# ESP32_with_USBC.net
KiCad netlist of a schematic drawn in Altium Designer
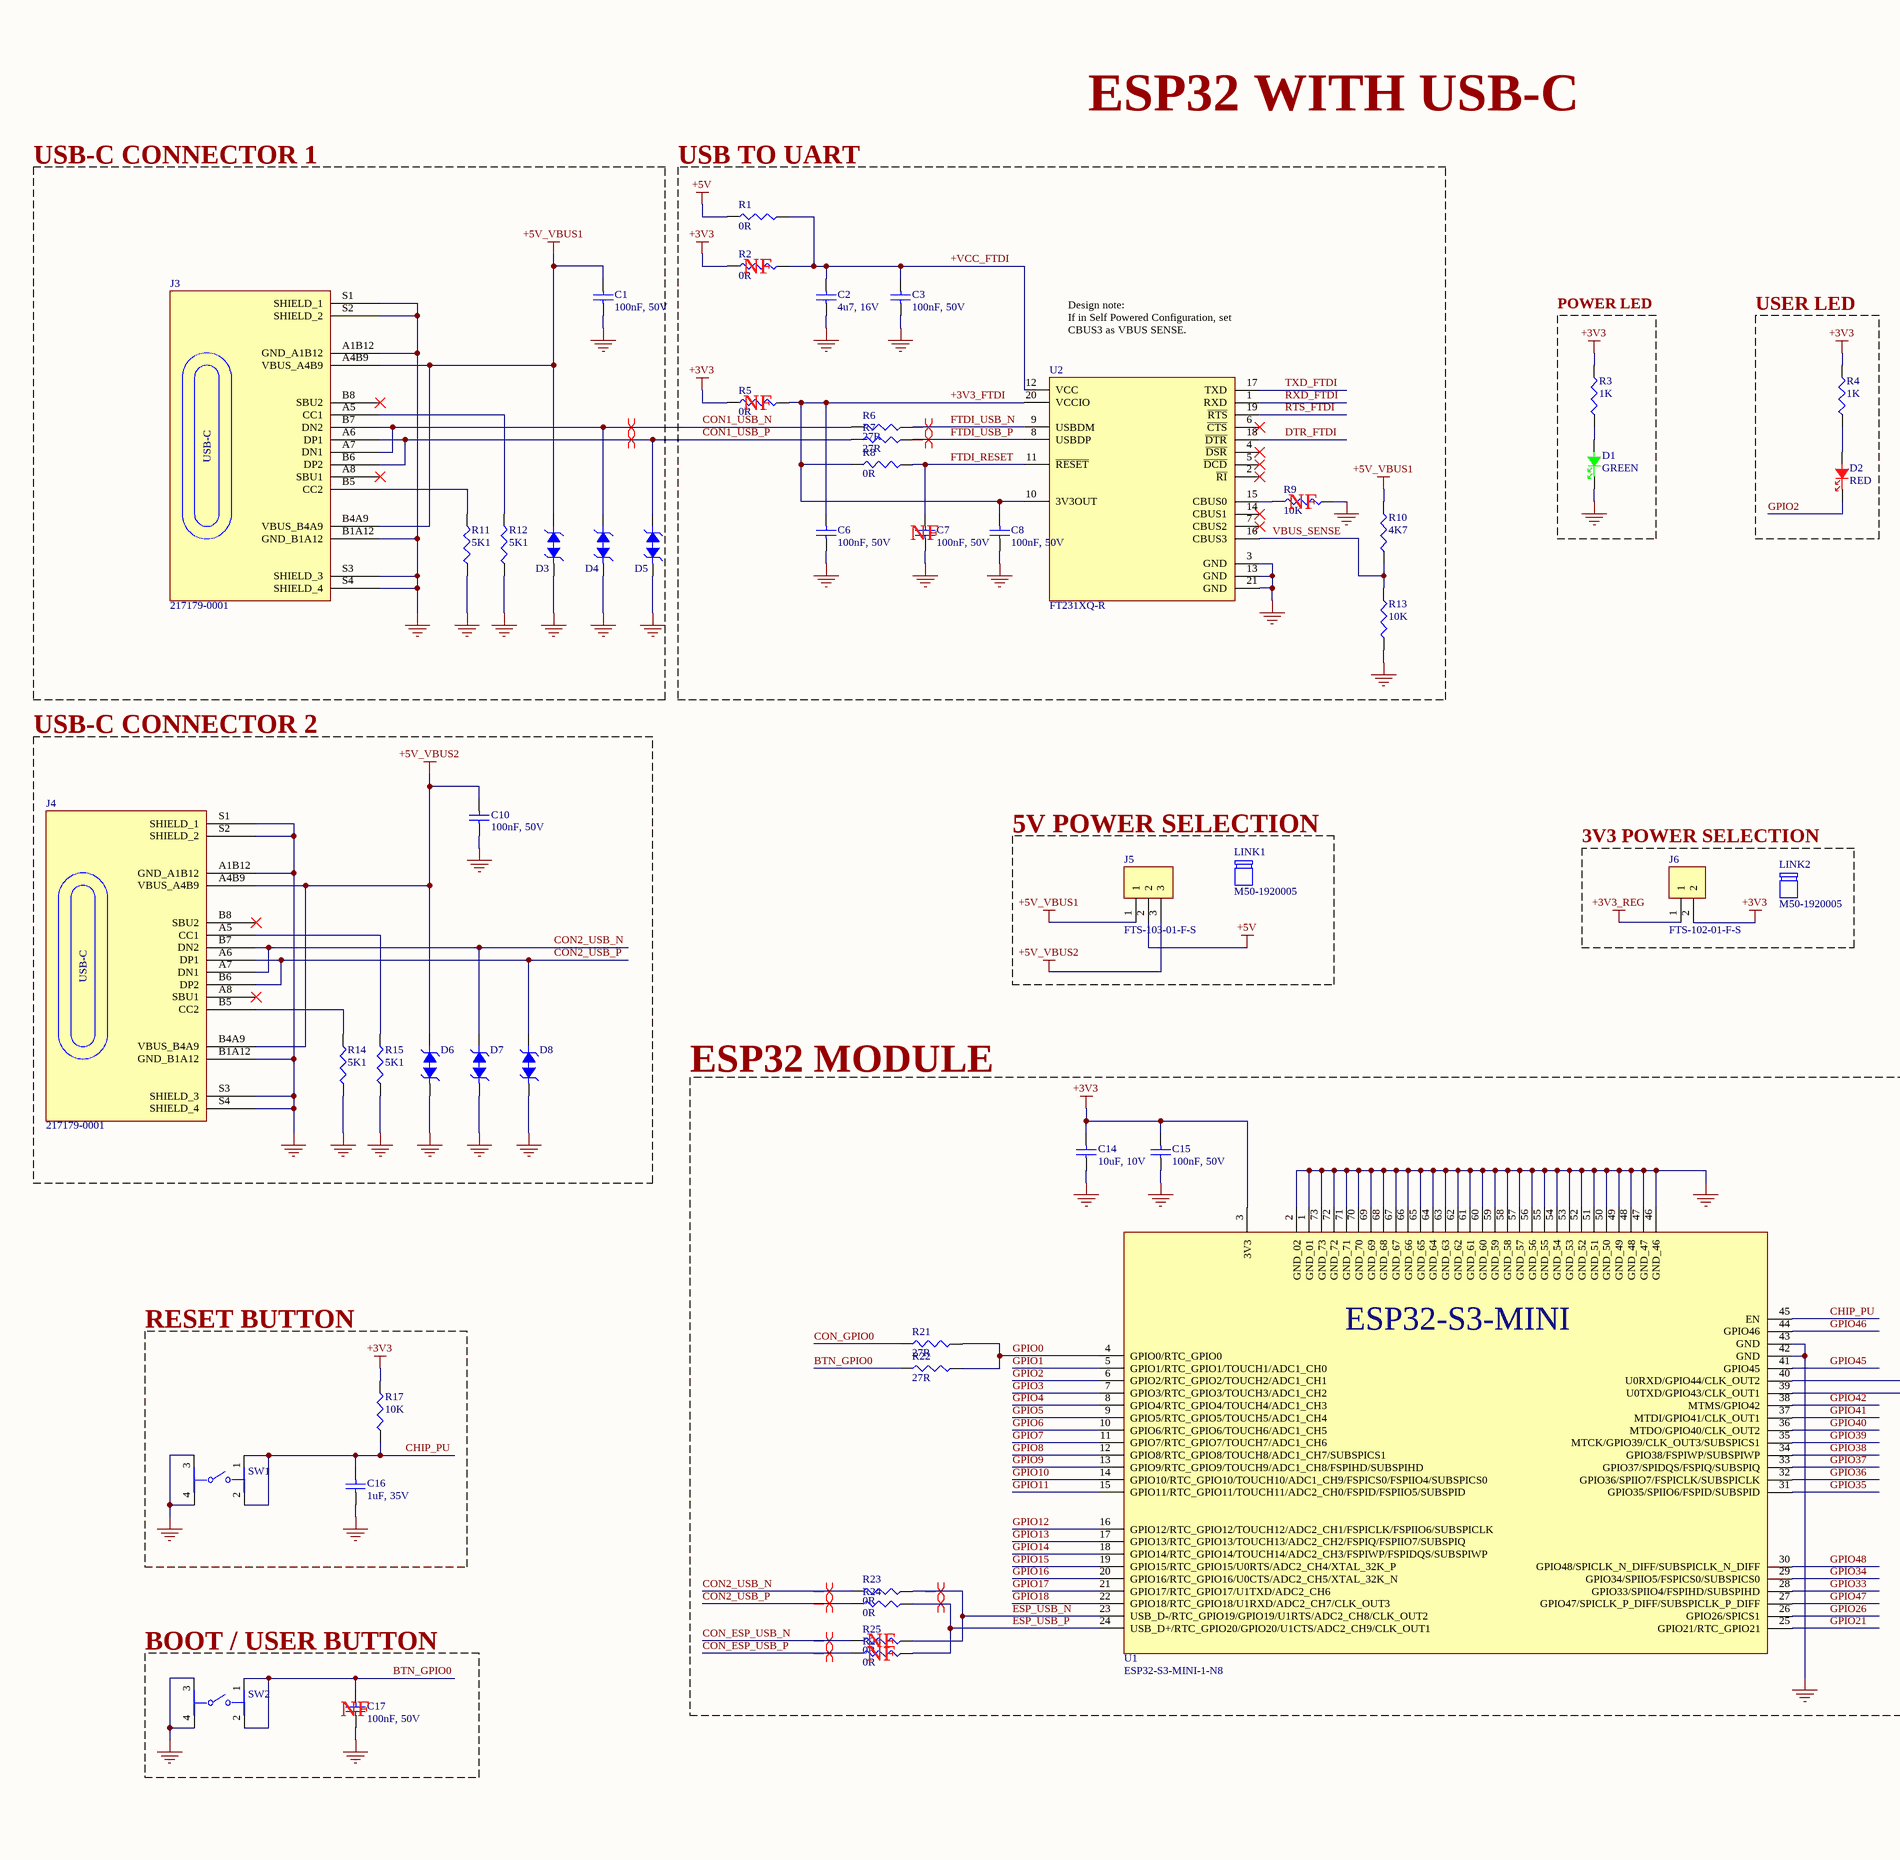
[diagram p0: ESP32 with USBC.SchDoc, left]
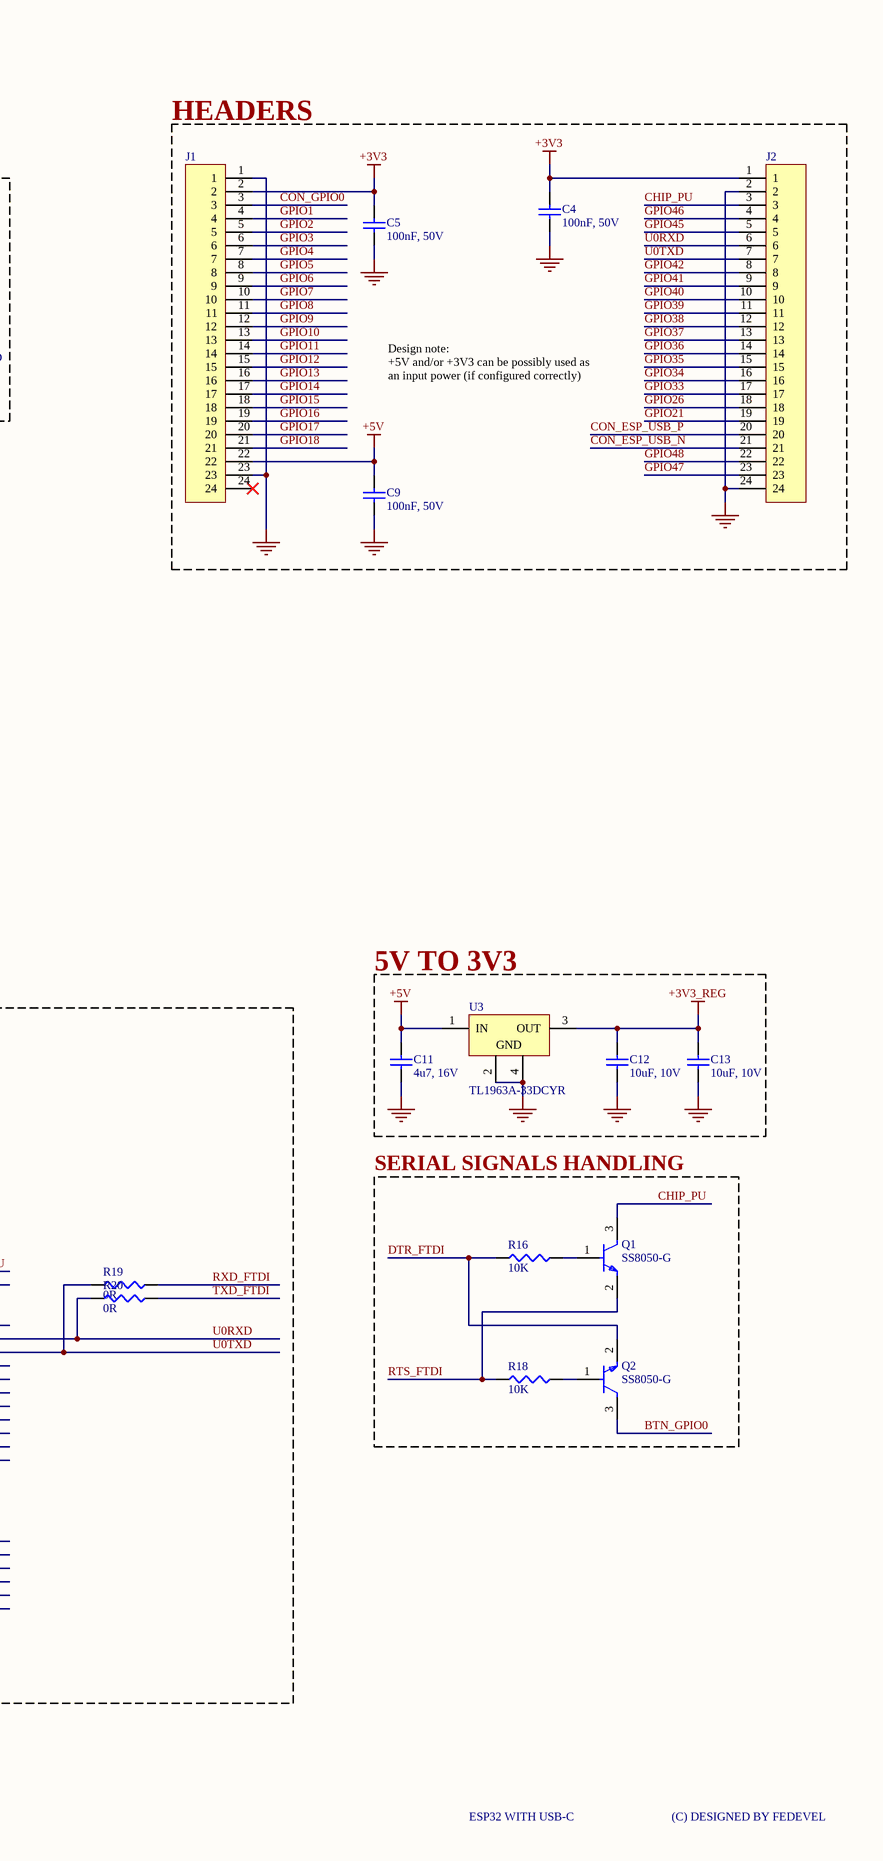
[diagram p1: ESP32 with USBC.SchDoc, right]

(export (version "E")
  (design (tool "Eeschema 10.0.6"))
  (components
    (comp (ref "C1")
      (value "100nF, 50V")
      (footprint "CAPC1005X55N")
      (description "CAP CER 0.1UF 50V X7R 0402")
      (fields
        (field (name "MANUFACTURER") "Samsung")
        (field (name "MANUFACTURER PART NUMBER") "CL05B104KB54PNC")
      )
      (libsource (lib "Schlib") (part "CL05B104KB54PNC"))
    )
    (comp (ref "C2")
      (value "4u7, 16V")
      (footprint "CAPC1005X55N")
      (description "CAP CER 4.7UF 16V X5R 0402")
      (fields
        (field (name "MANUFACTURER") "Samsung")
        (field (name "MANUFACTURER PART NUMBER") "CL05A475MO5NUNC")
      )
      (libsource (lib "Schlib") (part "CL05A475MO5NUNC"))
    )
    (comp (ref "C3")
      (value "100nF, 50V")
      (footprint "CAPC1005X55N")
      (description "CAP CER 0.1UF 50V X7R 0402")
      (fields
        (field (name "MANUFACTURER") "Samsung")
        (field (name "MANUFACTURER PART NUMBER") "CL05B104KB54PNC")
      )
      (libsource (lib "Schlib") (part "CL05B104KB54PNC"))
    )
    (comp (ref "C4")
      (value "100nF, 50V")
      (footprint "CAPC1005X55N")
      (description "CAP CER 0.1UF 50V X7R 0402")
      (fields
        (field (name "MANUFACTURER") "Samsung")
        (field (name "MANUFACTURER PART NUMBER") "CL05B104KB54PNC")
      )
      (libsource (lib "Schlib") (part "CL05B104KB54PNC"))
    )
    (comp (ref "C5")
      (value "100nF, 50V")
      (footprint "CAPC1005X55N")
      (description "CAP CER 0.1UF 50V X7R 0402")
      (fields
        (field (name "MANUFACTURER") "Samsung")
        (field (name "MANUFACTURER PART NUMBER") "CL05B104KB54PNC")
      )
      (libsource (lib "Schlib") (part "CL05B104KB54PNC"))
    )
    (comp (ref "C6")
      (value "100nF, 50V")
      (footprint "CAPC1005X55N")
      (description "CAP CER 0.1UF 50V X7R 0402")
      (fields
        (field (name "MANUFACTURER") "Samsung")
        (field (name "MANUFACTURER PART NUMBER") "CL05B104KB54PNC")
      )
      (libsource (lib "Schlib") (part "CL05B104KB54PNC"))
    )
    (comp (ref "C7")
      (value "100nF, 50V")
      (footprint "CAPC1005X55N")
      (description "CAP CER 0.1UF 50V X7R 0402")
      (fields
        (field (name "MANUFACTURER") "Samsung")
        (field (name "MANUFACTURER PART NUMBER") "CL05B104KB54PNC")
      )
      (libsource (lib "Schlib") (part "CL05B104KB54PNC"))
    )
    (comp (ref "C8")
      (value "100nF, 50V")
      (footprint "CAPC1005X55N")
      (description "CAP CER 0.1UF 50V X7R 0402")
      (fields
        (field (name "MANUFACTURER") "Samsung")
        (field (name "MANUFACTURER PART NUMBER") "CL05B104KB54PNC")
      )
      (libsource (lib "Schlib") (part "CL05B104KB54PNC"))
    )
    (comp (ref "C9")
      (value "100nF, 50V")
      (footprint "CAPC1005X55N")
      (description "CAP CER 0.1UF 50V X7R 0402")
      (fields
        (field (name "MANUFACTURER") "Samsung")
        (field (name "MANUFACTURER PART NUMBER") "CL05B104KB54PNC")
      )
      (libsource (lib "Schlib") (part "CL05B104KB54PNC"))
    )
    (comp (ref "C10")
      (value "100nF, 50V")
      (footprint "CAPC1005X55N")
      (description "CAP CER 0.1UF 50V X7R 0402")
      (fields
        (field (name "MANUFACTURER") "Samsung")
        (field (name "MANUFACTURER PART NUMBER") "CL05B104KB54PNC")
      )
      (libsource (lib "Schlib") (part "CL05B104KB54PNC"))
    )
    (comp (ref "C11")
      (value "4u7, 16V")
      (footprint "CAPC1005X55N")
      (description "CAP CER 4.7UF 16V X5R 0402")
      (fields
        (field (name "MANUFACTURER") "Samsung")
        (field (name "MANUFACTURER PART NUMBER") "CL05A475MO5NUNC")
      )
      (libsource (lib "Schlib") (part "CL05A475MO5NUNC"))
    )
    (comp (ref "C12")
      (value "10uF, 10V")
      (footprint "CAPC1005X55N")
      (description "CAP CER 10UF 10V X5R 0402")
      (fields
        (field (name "MANUFACTURER") "Samsung")
        (field (name "MANUFACTURER PART NUMBER") "CL05A106MP8NUB8")
      )
      (libsource (lib "Schlib") (part "CL05A106MP8NUB8"))
    )
    (comp (ref "C13")
      (value "10uF, 10V")
      (footprint "CAPC1005X55N")
      (description "CAP CER 10UF 10V X5R 0402")
      (fields
        (field (name "MANUFACTURER") "Samsung")
        (field (name "MANUFACTURER PART NUMBER") "CL05A106MP8NUB8")
      )
      (libsource (lib "Schlib") (part "CL05A106MP8NUB8"))
    )
    (comp (ref "C14")
      (value "10uF, 10V")
      (footprint "CAPC1005X55N")
      (description "CAP CER 10UF 10V X5R 0402")
      (fields
        (field (name "MANUFACTURER") "Samsung")
        (field (name "MANUFACTURER PART NUMBER") "CL05A106MP8NUB8")
      )
      (libsource (lib "Schlib") (part "CL05A106MP8NUB8"))
    )
    (comp (ref "C15")
      (value "100nF, 50V")
      (footprint "CAPC1005X55N")
      (description "CAP CER 0.1UF 50V X7R 0402")
      (fields
        (field (name "MANUFACTURER") "Samsung")
        (field (name "MANUFACTURER PART NUMBER") "CL05B104KB54PNC")
      )
      (libsource (lib "Schlib") (part "CL05B104KB54PNC"))
    )
    (comp (ref "C16")
      (value "1uF, 35V")
      (footprint "CAPC1005X55N")
      (description "CAP CER 1UF 35V X5R 0402")
      (fields
        (field (name "MANUFACTURER") "Samsung")
        (field (name "MANUFACTURER PART NUMBER") "CL05A105KL5NRNC")
      )
      (libsource (lib "Schlib") (part "CL05A105KL5NRNC"))
    )
    (comp (ref "C17")
      (value "100nF, 50V")
      (footprint "CAPC1005X55N")
      (description "CAP CER 0.1UF 50V X7R 0402")
      (fields
        (field (name "MANUFACTURER") "Samsung")
        (field (name "MANUFACTURER PART NUMBER") "CL05B104KB54PNC")
      )
      (libsource (lib "Schlib") (part "CL05B104KB54PNC"))
    )
    (comp (ref "D1")
      (value "GREEN")
      (footprint "LED0402G")
      (description "LED YLW-GRN 0402 SMD")
      (fields
        (field (name "MANUFACTURER") "Vishay")
        (field (name "MANUFACTURER PART NUMBER") "VLMG1500-GS08")
      )
      (libsource (lib "Schlib (1)") (part "VLMG1500-GS08"))
    )
    (comp (ref "D2")
      (value "RED")
      (footprint "LED0402R")
      (description "LED RED 0402 SMD")
      (fields
        (field (name "MANUFACTURER") "Vishay")
        (field (name "MANUFACTURER PART NUMBER") "VLMS1500-GS08")
      )
      (libsource (lib "Schlib (1)") (part "VLMS1500-GS08"))
    )
    (comp (ref "D3")
      (value "AQ3045-01ETG")
      (footprint "SOD882")
      (description "TVS DIODE 5.3VWM 12VC SOD882")
      (fields (field (name "MANUFACTURER") "Littelfuse") (field (name "LCSC PART NUMBER") "C3710326"))
      (libsource (lib "Schlib") (part "AQ3045-01ETG"))
    )
    (comp (ref "D4")
      (value "AQ3045-01ETG")
      (footprint "SOD882")
      (description "TVS DIODE 5.3VWM 12VC SOD882")
      (fields (field (name "MANUFACTURER") "Littelfuse") (field (name "LCSC PART NUMBER") "C3710326"))
      (libsource (lib "Schlib") (part "AQ3045-01ETG"))
    )
    (comp (ref "D5")
      (value "AQ3045-01ETG")
      (footprint "SOD882")
      (description "TVS DIODE 5.3VWM 12VC SOD882")
      (fields (field (name "MANUFACTURER") "Littelfuse") (field (name "LCSC PART NUMBER") "C3710326"))
      (libsource (lib "Schlib") (part "AQ3045-01ETG"))
    )
    (comp (ref "D6")
      (value "AQ3045-01ETG")
      (footprint "SOD882")
      (description "TVS DIODE 5.3VWM 12VC SOD882")
      (fields (field (name "MANUFACTURER") "Littelfuse") (field (name "LCSC PART NUMBER") "C3710326"))
      (libsource (lib "Schlib") (part "AQ3045-01ETG"))
    )
    (comp (ref "D7")
      (value "AQ3045-01ETG")
      (footprint "SOD882")
      (description "TVS DIODE 5.3VWM 12VC SOD882")
      (fields (field (name "MANUFACTURER") "Littelfuse") (field (name "LCSC PART NUMBER") "C3710326"))
      (libsource (lib "Schlib") (part "AQ3045-01ETG"))
    )
    (comp (ref "D8")
      (value "AQ3045-01ETG")
      (footprint "SOD882")
      (description "TVS DIODE 5.3VWM 12VC SOD882")
      (fields (field (name "MANUFACTURER") "Littelfuse") (field (name "LCSC PART NUMBER") "C3710326"))
      (libsource (lib "Schlib") (part "AQ3045-01ETG"))
    )
    (comp (ref "J1")
      (value "0022284245")
      (footprint "HDR_1X24_2.54MM")
      (description "CONN HEADER VERT 24POS 2.54MM")
      (fields (field (name "MANUFACTURER") "Molex") (field (name "LCSC PART NUMBER") "C7145888"))
      (libsource (lib "Schlib") (part "0022284245"))
    )
    (comp (ref "J2")
      (value "0022284245")
      (footprint "HDR_1X24_2.54MM")
      (description "CONN HEADER VERT 24POS 2.54MM")
      (fields (field (name "MANUFACTURER") "Molex") (field (name "LCSC PART NUMBER") "C7145888"))
      (libsource (lib "") (part "0022284245_1"))
    )
    (comp (ref "J3")
      (value "217179-0001")
      (footprint "FP-2171790001-MFG")
      (description "CONN RCP USB2.0 TYP C 24P SMD RA")
      (fields (field (name "MANUFACTURER") "Molex") (field (name "LCSC PART NUMBER") "C3197684"))
      (libsource (lib "Schlib") (part "217179-0001"))
    )
    (comp (ref "J4")
      (value "217179-0001")
      (footprint "FP-2171790001-MFG")
      (description "CONN RCP USB2.0 TYP C 24P SMD RA")
      (fields (field (name "MANUFACTURER") "Molex") (field (name "LCSC PART NUMBER") "C3197684"))
      (libsource (lib "Schlib") (part "217179-0001"))
    )
    (comp (ref "J5")
      (value "FTS-103-01-F-S")
      (footprint "HDR_1X3_1.27MM")
      (description "CONN HEADER VERT 3POS 1.27MM")
      (fields (field (name "MANUFACTURER") "Samtec") (field (name "LCSC PART NUMBER") "C3333578"))
      (libsource (lib "Schlib") (part "FTS-103-01-F-S"))
    )
    (comp (ref "J6")
      (value "FTS-102-01-F-S")
      (footprint "HDR_1X2_1.27MM")
      (description "CONN HEADER VERT 2POS 1.27MM")
      (fields (field (name "MANUFACTURER") "Samtec") (field (name "LCSC PART NUMBER") "C6045317"))
      (libsource (lib "Schlib") (part "FTS-102-01-F-S"))
    )
    (comp (ref "LINK1")
      (value "M50-1920005")
      (description "CONN SHUNT 1.27MM RED")
      (fields (field (name "MANUFACTURER") "Harwin") (field (name "LCSC PART NUMBER") "C6985646"))
      (libsource (lib "Schlib") (part "M50-1920005"))
    )
    (comp (ref "LINK2")
      (value "M50-1920005")
      (description "CONN SHUNT 1.27MM RED")
      (fields (field (name "MANUFACTURER") "Harwin") (field (name "LCSC PART NUMBER") "C6985646"))
      (libsource (lib "Schlib") (part "M50-1920005"))
    )
    (comp (ref "Q1")
      (value "SS8050-G")
      (footprint "FP-SS8050-G-IPC_B")
      (description "TRANS NPN 25V 1.5A SOT23-3")
      (fields (field (name "MANUFACTURER") "Comchip") (field (name "LCSC PART NUMBER") "C164886"))
      (libsource (lib "Schlib") (part "SS8050-G"))
    )
    (comp (ref "Q2")
      (value "SS8050-G")
      (footprint "FP-SS8050-G-IPC_B")
      (description "TRANS NPN 25V 1.5A SOT23-3")
      (fields (field (name "MANUFACTURER") "Comchip") (field (name "LCSC PART NUMBER") "C164886"))
      (libsource (lib "Schlib") (part "SS8050-G"))
    )
    (comp (ref "R1")
      (value "0R")
      (footprint "RESC1005X37N")
      (description "RES 0 OHM JUMPER 1/16W 0402")
      (fields
        (field (name "MANUFACTURER") "Yageo")
        (field (name "MANUFACTURER PART NUMBER") "RC0402JR-070RL")
      )
      (libsource (lib "Schlib") (part "RC0402JR-070RL"))
    )
    (comp (ref "R2")
      (value "0R")
      (footprint "RESC1005X37N")
      (description "RES 0 OHM JUMPER 1/16W 0402")
      (fields
        (field (name "MANUFACTURER") "Yageo")
        (field (name "MANUFACTURER PART NUMBER") "RC0402JR-070RL")
      )
      (libsource (lib "Schlib") (part "RC0402JR-070RL"))
    )
    (comp (ref "R3")
      (value "1K")
      (footprint "RESC1005X37N")
      (description "RES 1K OHM 1% 1/16W 0402")
      (fields
        (field (name "MANUFACTURER") "Yageo")
        (field (name "MANUFACTURER PART NUMBER") "RC0402FR-071KL")
      )
      (libsource (lib "Schlib") (part "RC0402FR-071KL"))
    )
    (comp (ref "R4")
      (value "1K")
      (footprint "RESC1005X37N")
      (description "RES 1K OHM 1% 1/16W 0402")
      (fields
        (field (name "MANUFACTURER") "Yageo")
        (field (name "MANUFACTURER PART NUMBER") "RC0402FR-071KL")
      )
      (libsource (lib "Schlib") (part "RC0402FR-071KL"))
    )
    (comp (ref "R5")
      (value "0R")
      (footprint "RESC1005X37N")
      (description "RES 0 OHM JUMPER 1/16W 0402")
      (fields
        (field (name "MANUFACTURER") "Yageo")
        (field (name "MANUFACTURER PART NUMBER") "RC0402JR-070RL")
      )
      (libsource (lib "Schlib") (part "RC0402JR-070RL"))
    )
    (comp (ref "R6")
      (value "27R")
      (footprint "RESC1005X37N")
      (description "RES 27 OHM 1% 1/16W 0402")
      (fields
        (field (name "MANUFACTURER") "Yageo")
        (field (name "MANUFACTURER PART NUMBER") "RC0402FR-0727RL")
      )
      (libsource (lib "Schlib") (part "RC0402FR-0727RL"))
    )
    (comp (ref "R7")
      (value "27R")
      (footprint "RESC1005X37N")
      (description "RES 27 OHM 1% 1/16W 0402")
      (fields
        (field (name "MANUFACTURER") "Yageo")
        (field (name "MANUFACTURER PART NUMBER") "RC0402FR-0727RL")
      )
      (libsource (lib "Schlib") (part "RC0402FR-0727RL"))
    )
    (comp (ref "R8")
      (value "0R")
      (footprint "RESC1005X37N")
      (description "RES 0 OHM JUMPER 1/16W 0402")
      (fields
        (field (name "MANUFACTURER") "Yageo")
        (field (name "MANUFACTURER PART NUMBER") "RC0402JR-070RL")
      )
      (libsource (lib "Schlib") (part "RC0402JR-070RL"))
    )
    (comp (ref "R9")
      (value "10K")
      (footprint "RESC1005X37N")
      (description "RES SMD 10K OHM 1% 1/16W 0402")
      (fields
        (field (name "MANUFACTURER") "Yageo")
        (field (name "MANUFACTURER PART NUMBER") "AC0402FR-0710KL")
      )
      (libsource (lib "Schlib") (part "AC0402FR-0710KL"))
    )
    (comp (ref "R10")
      (value "4K7")
      (footprint "RESC1005X37N")
      (description "RES 4.7K OHM 1% 1/16W 0402")
      (fields
        (field (name "MANUFACTURER") "Yageo")
        (field (name "MANUFACTURER PART NUMBER") "RC0402FR-074K7L")
      )
      (libsource (lib "Schlib") (part "RC0402FR-074K7L"))
    )
    (comp (ref "R11")
      (value "5K1")
      (footprint "RESC1005X37N")
      (description "RES SMD 5.1K OHM 1% 1/16W 0402")
      (fields
        (field (name "MANUFACTURER") "Yageo")
        (field (name "MANUFACTURER PART NUMBER") "AC0402FR-075K1L")
      )
      (libsource (lib "Schlib") (part "AC0402FR-075K1L"))
    )
    (comp (ref "R12")
      (value "5K1")
      (footprint "RESC1005X37N")
      (description "RES SMD 5.1K OHM 1% 1/16W 0402")
      (fields
        (field (name "MANUFACTURER") "Yageo")
        (field (name "MANUFACTURER PART NUMBER") "AC0402FR-075K1L")
      )
      (libsource (lib "Schlib") (part "AC0402FR-075K1L"))
    )
    (comp (ref "R13")
      (value "10K")
      (footprint "RESC1005X37N")
      (description "RES SMD 10K OHM 1% 1/16W 0402")
      (fields
        (field (name "MANUFACTURER") "Yageo")
        (field (name "MANUFACTURER PART NUMBER") "AC0402FR-0710KL")
      )
      (libsource (lib "Schlib") (part "AC0402FR-0710KL"))
    )
    (comp (ref "R14")
      (value "5K1")
      (footprint "RESC1005X37N")
      (description "RES SMD 5.1K OHM 1% 1/16W 0402")
      (fields
        (field (name "MANUFACTURER") "Yageo")
        (field (name "MANUFACTURER PART NUMBER") "AC0402FR-075K1L")
      )
      (libsource (lib "Schlib") (part "AC0402FR-075K1L"))
    )
    (comp (ref "R15")
      (value "5K1")
      (footprint "RESC1005X37N")
      (description "RES SMD 5.1K OHM 1% 1/16W 0402")
      (fields
        (field (name "MANUFACTURER") "Yageo")
        (field (name "MANUFACTURER PART NUMBER") "AC0402FR-075K1L")
      )
      (libsource (lib "Schlib") (part "AC0402FR-075K1L"))
    )
    (comp (ref "R16")
      (value "10K")
      (footprint "RESC1005X37N")
      (description "RES SMD 10K OHM 1% 1/16W 0402")
      (fields
        (field (name "MANUFACTURER") "Yageo")
        (field (name "MANUFACTURER PART NUMBER") "AC0402FR-0710KL")
      )
      (libsource (lib "Schlib") (part "AC0402FR-0710KL"))
    )
    (comp (ref "R17")
      (value "10K")
      (footprint "RESC1005X37N")
      (description "RES SMD 10K OHM 1% 1/16W 0402")
      (fields
        (field (name "MANUFACTURER") "Yageo")
        (field (name "MANUFACTURER PART NUMBER") "AC0402FR-0710KL")
      )
      (libsource (lib "Schlib") (part "AC0402FR-0710KL"))
    )
    (comp (ref "R18")
      (value "10K")
      (footprint "RESC1005X37N")
      (description "RES SMD 10K OHM 1% 1/16W 0402")
      (fields
        (field (name "MANUFACTURER") "Yageo")
        (field (name "MANUFACTURER PART NUMBER") "AC0402FR-0710KL")
      )
      (libsource (lib "Schlib") (part "AC0402FR-0710KL"))
    )
    (comp (ref "R19")
      (value "0R")
      (footprint "RESC1005X37N")
      (description "RES 0 OHM JUMPER 1/16W 0402")
      (fields
        (field (name "MANUFACTURER") "Yageo")
        (field (name "MANUFACTURER PART NUMBER") "RC0402JR-070RL")
      )
      (libsource (lib "Schlib") (part "RC0402JR-070RL"))
    )
    (comp (ref "R20")
      (value "0R")
      (footprint "RESC1005X37N")
      (description "RES 0 OHM JUMPER 1/16W 0402")
      (fields
        (field (name "MANUFACTURER") "Yageo")
        (field (name "MANUFACTURER PART NUMBER") "RC0402JR-070RL")
      )
      (libsource (lib "Schlib") (part "RC0402JR-070RL"))
    )
    (comp (ref "R21")
      (value "27R")
      (footprint "RESC1005X37N")
      (description "RES 27 OHM 1% 1/16W 0402")
      (fields
        (field (name "MANUFACTURER") "Yageo")
        (field (name "MANUFACTURER PART NUMBER") "RC0402FR-0727RL")
      )
      (libsource (lib "Schlib") (part "RC0402FR-0727RL"))
    )
    (comp (ref "R22")
      (value "27R")
      (footprint "RESC1005X37N")
      (description "RES 27 OHM 1% 1/16W 0402")
      (fields
        (field (name "MANUFACTURER") "Yageo")
        (field (name "MANUFACTURER PART NUMBER") "RC0402FR-0727RL")
      )
      (libsource (lib "Schlib") (part "RC0402FR-0727RL"))
    )
    (comp (ref "R23")
      (value "0R")
      (footprint "RESC1005X37N")
      (description "RES 0 OHM JUMPER 1/16W 0402")
      (fields
        (field (name "MANUFACTURER") "Yageo")
        (field (name "MANUFACTURER PART NUMBER") "RC0402JR-070RL")
      )
      (libsource (lib "Schlib") (part "RC0402JR-070RL"))
    )
    (comp (ref "R24")
      (value "0R")
      (footprint "RESC1005X37N")
      (description "RES 0 OHM JUMPER 1/16W 0402")
      (fields
        (field (name "MANUFACTURER") "Yageo")
        (field (name "MANUFACTURER PART NUMBER") "RC0402JR-070RL")
      )
      (libsource (lib "Schlib") (part "RC0402JR-070RL"))
    )
    (comp (ref "R25")
      (value "0R")
      (footprint "RESC1005X37N")
      (description "RES 0 OHM JUMPER 1/16W 0402")
      (fields
        (field (name "MANUFACTURER") "Yageo")
        (field (name "MANUFACTURER PART NUMBER") "RC0402JR-070RL")
      )
      (libsource (lib "Schlib") (part "RC0402JR-070RL"))
    )
    (comp (ref "R26")
      (value "0R")
      (footprint "RESC1005X37N")
      (description "RES 0 OHM JUMPER 1/16W 0402")
      (fields
        (field (name "MANUFACTURER") "Yageo")
        (field (name "MANUFACTURER PART NUMBER") "RC0402JR-070RL")
      )
      (libsource (lib "Schlib") (part "RC0402JR-070RL"))
    )
    (comp (ref "SW1")
      (value "PTS645SH50SMTR92LFS")
      (footprint "FP-PTS645SH50SMTR92LFS-MFG")
      (description "SWITCH TACTILE SPST-NO 0.05A 12V")
      (fields (field (name "MANUFACTURER") "ITT C&K") (field (name "LCSC PART NUMBER") "C221869"))
      (libsource (lib "Schlib") (part "PTS645SH50SMTR92LFS"))
    )
    (comp (ref "SW2")
      (value "PTS645SH50SMTR92LFS")
      (footprint "FP-PTS645SH50SMTR92LFS-MFG")
      (description "SWITCH TACTILE SPST-NO 0.05A 12V")
      (fields (field (name "MANUFACTURER") "ITT C&K") (field (name "LCSC PART NUMBER") "C221869"))
      (libsource (lib "Schlib") (part "PTS645SH50SMTR92LFS"))
    )
    (comp (ref "U1")
      (value "ESP32-S3-MINI-1-N8")
      (footprint "XCVR_ESP32-S3-MINI-1-N8")
      (description "SMD Module, ESP32-S3FN8, 8 mb Sp")
      (fields (field (name "MANUFACTURER") "Espressif Systems") (field (name "LCSC PART NUMBER") "C2913206"))
      (libsource (lib "Schlib") (part "ESP32-S3-MINI-1-N8"))
    )
    (comp (ref "U2")
      (value "FT231XQ-R")
      (footprint "FP-QFN-20-IPC_B")
      (description "IC USB SERIAL FULL UART 20QFN")
      (fields (field (name "MANUFACTURER") "FTDI") (field (name "LCSC PART NUMBER") "C132159"))
      (libsource (lib "Schlib") (part "FT231XQ-R"))
    )
    (comp (ref "U3")
      (value "TL1963A-33DCYR")
      (footprint "DCY0004A_N")
      (description "IC REG LINEAR 3.3V 1.5A SOT223-4")
      (fields (field (name "MANUFACTURER") "Texas Instruments") (field (name "LCSC PART NUMBER") "C181262"))
      (libsource (lib "Schlib") (part "TL1963A-33DCYR"))
    )
  )
  (nets
    (net (code "1") (name "+3V3") (class "Default")
      (node (ref "C14") (pin "2") (pinfunction "2_2") (pintype "passive"))
      (node (ref "C15") (pin "2") (pinfunction "2_2") (pintype "passive"))
      (node (ref "C4") (pin "2") (pinfunction "2_2") (pintype "passive"))
      (node (ref "C5") (pin "2") (pinfunction "2_2") (pintype "passive"))
      (node (ref "J1") (pin "2") (pinfunction "2_2") (pintype "passive"))
      (node (ref "J2") (pin "1") (pinfunction "1_1") (pintype "passive"))
      (node (ref "J6") (pin "2") (pinfunction "2_2") (pintype "passive"))
      (node (ref "R17") (pin "2") (pinfunction "2_2") (pintype "passive"))
      (node (ref "R2") (pin "1") (pinfunction "1_1") (pintype "passive"))
      (node (ref "R3") (pin "2") (pinfunction "2_2") (pintype "passive"))
      (node (ref "R4") (pin "2") (pinfunction "2_2") (pintype "passive"))
      (node (ref "R5") (pin "1") (pinfunction "1_1") (pintype "passive"))
      (node (ref "U1") (pin "3") (pinfunction "3V3_3") (pintype "passive"))
    )
    (net (code "2") (name "+3V3_REG") (class "Default")
      (node (ref "C12") (pin "2") (pinfunction "2_2") (pintype "passive"))
      (node (ref "C13") (pin "2") (pinfunction "2_2") (pintype "passive"))
      (node (ref "J6") (pin "1") (pinfunction "1_1") (pintype "passive"))
      (node (ref "U3") (pin "3") (pinfunction "OUT_3") (pintype "power_in"))
    )
    (net (code "3") (name "+5V") (class "Default")
      (node (ref "C11") (pin "2") (pinfunction "2_2") (pintype "passive"))
      (node (ref "C9") (pin "2") (pinfunction "2_2") (pintype "passive"))
      (node (ref "J1") (pin "22") (pinfunction "22_22") (pintype "passive"))
      (node (ref "J5") (pin "2") (pinfunction "2_2") (pintype "passive"))
      (node (ref "R1") (pin "1") (pinfunction "1_1") (pintype "passive"))
      (node (ref "U3") (pin "1") (pinfunction "IN_1") (pintype "power_in"))
    )
    (net (code "4") (name "+5V_VBUS1") (class "Default")
      (node (ref "C1") (pin "2") (pinfunction "2_2") (pintype "passive"))
      (node (ref "D3") (pin "2") (pinfunction "2_2") (pintype "passive"))
      (node (ref "J3") (pin "A4B9") (pinfunction "VBUS_A4B9_A4B9") (pintype "passive"))
      (node (ref "J3") (pin "B4A9") (pinfunction "VBUS_B4A9_B4A9") (pintype "passive"))
      (node (ref "J5") (pin "1") (pinfunction "1_1") (pintype "passive"))
      (node (ref "R10") (pin "2") (pinfunction "2_2") (pintype "passive"))
    )
    (net (code "5") (name "+5V_VBUS2") (class "Default")
      (node (ref "C10") (pin "2") (pinfunction "2_2") (pintype "passive"))
      (node (ref "D6") (pin "2") (pinfunction "2_2") (pintype "passive"))
      (node (ref "J4") (pin "A4B9") (pinfunction "VBUS_A4B9_A4B9") (pintype "passive"))
      (node (ref "J4") (pin "B4A9") (pinfunction "VBUS_B4A9_B4A9") (pintype "passive"))
      (node (ref "J5") (pin "3") (pinfunction "3_3") (pintype "passive"))
    )
    (net (code "6") (name "/+3V3_FTDI") (class "Default")
      (node (ref "C6") (pin "2") (pinfunction "2_2") (pintype "passive"))
      (node (ref "C8") (pin "2") (pinfunction "2_2") (pintype "passive"))
      (node (ref "R5") (pin "2") (pinfunction "2_2") (pintype "passive"))
      (node (ref "R8") (pin "1") (pinfunction "1_1") (pintype "passive"))
      (node (ref "U2") (pin "10") (pinfunction "3V3OUT_10") (pintype "passive"))
      (node (ref "U2") (pin "20") (pinfunction "VCCIO_20") (pintype "passive"))
    )
    (net (code "7") (name "/+VCC_FTDI") (class "Default")
      (node (ref "C2") (pin "2") (pinfunction "2_2") (pintype "passive"))
      (node (ref "C3") (pin "2") (pinfunction "2_2") (pintype "passive"))
      (node (ref "R1") (pin "2") (pinfunction "2_2") (pintype "passive"))
      (node (ref "R2") (pin "2") (pinfunction "2_2") (pintype "passive"))
      (node (ref "U2") (pin "12") (pinfunction "VCC_12") (pintype "passive"))
    )
    (net (code "8") (name "/BTN_GPIO0") (class "Default")
      (node (ref "C17") (pin "2") (pinfunction "2_2") (pintype "passive"))
      (node (ref "Q2") (pin "3") (pinfunction "C_3") (pintype "passive"))
      (node (ref "R22") (pin "1") (pinfunction "1_1") (pintype "passive"))
      (node (ref "SW2") (pin "1") (pinfunction "1_1") (pintype "passive"))
      (node (ref "SW2") (pin "2") (pinfunction "2_2") (pintype "passive"))
    )
    (net (code "9") (name "/CHIP_PU") (class "Default")
      (node (ref "C16") (pin "2") (pinfunction "2_2") (pintype "passive"))
      (node (ref "J2") (pin "3") (pinfunction "3_3") (pintype "passive"))
      (node (ref "Q1") (pin "3") (pinfunction "C_3") (pintype "passive"))
      (node (ref "R17") (pin "1") (pinfunction "1_1") (pintype "passive"))
      (node (ref "SW1") (pin "1") (pinfunction "1_1") (pintype "passive"))
      (node (ref "SW1") (pin "2") (pinfunction "2_2") (pintype "passive"))
      (node (ref "U1") (pin "45") (pinfunction "EN_45") (pintype "passive"))
    )
    (net (code "10") (name "/CON1_USB_N") (class "Default")
      (node (ref "D4") (pin "2") (pinfunction "2_2") (pintype "passive"))
      (node (ref "J3") (pin "A7") (pinfunction "DN1_A7") (pintype "passive"))
      (node (ref "J3") (pin "B7") (pinfunction "DN2_B7") (pintype "passive"))
      (node (ref "R6") (pin "1") (pinfunction "1_1") (pintype "passive"))
    )
    (net (code "11") (name "/CON1_USB_P") (class "Default")
      (node (ref "D5") (pin "2") (pinfunction "2_2") (pintype "passive"))
      (node (ref "J3") (pin "A6") (pinfunction "DP1_A6") (pintype "passive"))
      (node (ref "J3") (pin "B6") (pinfunction "DP2_B6") (pintype "passive"))
      (node (ref "R7") (pin "1") (pinfunction "1_1") (pintype "passive"))
    )
    (net (code "12") (name "/CON2_USB_N") (class "Default")
      (node (ref "D7") (pin "2") (pinfunction "2_2") (pintype "passive"))
      (node (ref "J4") (pin "A7") (pinfunction "DN1_A7") (pintype "passive"))
      (node (ref "J4") (pin "B7") (pinfunction "DN2_B7") (pintype "passive"))
      (node (ref "R23") (pin "1") (pinfunction "1_1") (pintype "passive"))
    )
    (net (code "13") (name "/CON2_USB_P") (class "Default")
      (node (ref "D8") (pin "2") (pinfunction "2_2") (pintype "passive"))
      (node (ref "J4") (pin "A6") (pinfunction "DP1_A6") (pintype "passive"))
      (node (ref "J4") (pin "B6") (pinfunction "DP2_B6") (pintype "passive"))
      (node (ref "R24") (pin "1") (pinfunction "1_1") (pintype "passive"))
    )
    (net (code "14") (name "/CON_ESP_USB_N") (class "Default")
      (node (ref "J2") (pin "21") (pinfunction "21_21") (pintype "passive"))
      (node (ref "R25") (pin "1") (pinfunction "1_1") (pintype "passive"))
    )
    (net (code "15") (name "/CON_ESP_USB_P") (class "Default")
      (node (ref "J2") (pin "20") (pinfunction "20_20") (pintype "passive"))
      (node (ref "R26") (pin "1") (pinfunction "1_1") (pintype "passive"))
    )
    (net (code "16") (name "/CON_GPIO0") (class "Default")
      (node (ref "J1") (pin "3") (pinfunction "3_3") (pintype "passive"))
      (node (ref "R21") (pin "1") (pinfunction "1_1") (pintype "passive"))
    )
    (net (code "17") (name "/DTR_FTDI") (class "Default")
      (node (ref "Q2") (pin "2") (pinfunction "E_2") (pintype "passive"))
      (node (ref "R16") (pin "1") (pinfunction "1_1") (pintype "passive"))
      (node (ref "U2") (pin "18") (pinfunction "~{DTR}_18") (pintype "passive"))
    )
    (net (code "18") (name "/ESP_USB_N") (class "Default")
      (node (ref "R23") (pin "2") (pinfunction "2_2") (pintype "passive"))
      (node (ref "R25") (pin "2") (pinfunction "2_2") (pintype "passive"))
      (node (ref "U1") (pin "23") (pinfunction "USB_D-/RTC_GPIO19/GPIO19/U1RTS/ADC2_CH8/CLK_OUT2_23") (pintype "passive"))
    )
    (net (code "19") (name "/ESP_USB_P") (class "Default")
      (node (ref "R24") (pin "2") (pinfunction "2_2") (pintype "passive"))
      (node (ref "R26") (pin "2") (pinfunction "2_2") (pintype "passive"))
      (node (ref "U1") (pin "24") (pinfunction "USB_D+/RTC_GPIO20/GPIO20/U1CTS/ADC2_CH9/CLK_OUT1_24") (pintype "passive"))
    )
    (net (code "20") (name "/FTDI_RESET") (class "Default")
      (node (ref "C7") (pin "2") (pinfunction "2_2") (pintype "passive"))
      (node (ref "R8") (pin "2") (pinfunction "2_2") (pintype "passive"))
      (node (ref "U2") (pin "11") (pinfunction "~{RESET}_11") (pintype "passive"))
    )
    (net (code "21") (name "/FTDI_USB_N") (class "Default")
      (node (ref "R6") (pin "2") (pinfunction "2_2") (pintype "passive"))
      (node (ref "U2") (pin "9") (pinfunction "USBDM_9") (pintype "passive"))
    )
    (net (code "22") (name "/FTDI_USB_P") (class "Default")
      (node (ref "R7") (pin "2") (pinfunction "2_2") (pintype "passive"))
      (node (ref "U2") (pin "8") (pinfunction "USBDP_8") (pintype "passive"))
    )
    (net (code "23") (name "/GPIO0") (class "Default")
      (node (ref "R21") (pin "2") (pinfunction "2_2") (pintype "passive"))
      (node (ref "R22") (pin "2") (pinfunction "2_2") (pintype "passive"))
      (node (ref "U1") (pin "4") (pinfunction "GPIO0/RTC_GPIO0_4") (pintype "passive"))
    )
    (net (code "24") (name "/GPIO1") (class "Default")
      (node (ref "J1") (pin "4") (pinfunction "4_4") (pintype "passive"))
      (node (ref "U1") (pin "5") (pinfunction "GPIO1/RTC_GPIO1/TOUCH1/ADC1_CH0_5") (pintype "passive"))
    )
    (net (code "25") (name "/GPIO2") (class "Default")
      (node (ref "D2") (pin "1") (pinfunction "1_1") (pintype "passive"))
      (node (ref "J1") (pin "5") (pinfunction "5_5") (pintype "passive"))
      (node (ref "U1") (pin "6") (pinfunction "GPIO2/RTC_GPIO2/TOUCH2/ADC1_CH1_6") (pintype "passive"))
    )
    (net (code "26") (name "/GPIO3") (class "Default")
      (node (ref "J1") (pin "6") (pinfunction "6_6") (pintype "passive"))
      (node (ref "U1") (pin "7") (pinfunction "GPIO3/RTC_GPIO3/TOUCH3/ADC1_CH2_7") (pintype "passive"))
    )
    (net (code "27") (name "/GPIO4") (class "Default")
      (node (ref "J1") (pin "7") (pinfunction "7_7") (pintype "passive"))
      (node (ref "U1") (pin "8") (pinfunction "GPIO4/RTC_GPIO4/TOUCH4/ADC1_CH3_8") (pintype "passive"))
    )
    (net (code "28") (name "/GPIO5") (class "Default")
      (node (ref "J1") (pin "8") (pinfunction "8_8") (pintype "passive"))
      (node (ref "U1") (pin "9") (pinfunction "GPIO5/RTC_GPIO5/TOUCH5/ADC1_CH4_9") (pintype "passive"))
    )
    (net (code "29") (name "/GPIO6") (class "Default")
      (node (ref "J1") (pin "9") (pinfunction "9_9") (pintype "passive"))
      (node (ref "U1") (pin "10") (pinfunction "GPIO6/RTC_GPIO6/TOUCH6/ADC1_CH5_10") (pintype "passive"))
    )
    (net (code "30") (name "/GPIO7") (class "Default")
      (node (ref "J1") (pin "10") (pinfunction "10_10") (pintype "passive"))
      (node (ref "U1") (pin "11") (pinfunction "GPIO7/RTC_GPIO7/TOUCH7/ADC1_CH6_11") (pintype "passive"))
    )
    (net (code "31") (name "/GPIO8") (class "Default")
      (node (ref "J1") (pin "11") (pinfunction "11_11") (pintype "passive"))
      (node (ref "U1") (pin "12") (pinfunction "GPIO8/RTC_GPIO8/TOUCH8/ADC1_CH7/SUBSPICS1_12") (pintype "passive"))
    )
    (net (code "32") (name "/GPIO9") (class "Default")
      (node (ref "J1") (pin "12") (pinfunction "12_12") (pintype "passive"))
      (node (ref "U1") (pin "13") (pinfunction "GPIO9/RTC_GPIO9/TOUCH9/ADC1_CH8/FSPIHD/SUBSPIHD_13") (pintype "passive"))
    )
    (net (code "33") (name "/GPIO10") (class "Default")
      (node (ref "J1") (pin "13") (pinfunction "13_13") (pintype "passive"))
      (node (ref "U1") (pin "14") (pinfunction "GPIO10/RTC_GPIO10/TOUCH10/ADC1_CH9/FSPICS0/FSPIIO4/SUBSPICS0_14") (pintype "passive"))
    )
    (net (code "34") (name "/GPIO11") (class "Default")
      (node (ref "J1") (pin "14") (pinfunction "14_14") (pintype "passive"))
      (node (ref "U1") (pin "15") (pinfunction "GPIO11/RTC_GPIO11/TOUCH11/ADC2_CH0/FSPID/FSPIIO5/SUBSPID_15") (pintype "passive"))
    )
    (net (code "35") (name "/GPIO12") (class "Default")
      (node (ref "J1") (pin "15") (pinfunction "15_15") (pintype "passive"))
      (node (ref "U1") (pin "16") (pinfunction "GPIO12/RTC_GPIO12/TOUCH12/ADC2_CH1/FSPICLK/FSPIIO6/SUBSPICLK_16") (pintype "passive"))
    )
    (net (code "36") (name "/GPIO13") (class "Default")
      (node (ref "J1") (pin "16") (pinfunction "16_16") (pintype "passive"))
      (node (ref "U1") (pin "17") (pinfunction "GPIO13/RTC_GPIO13/TOUCH13/ADC2_CH2/FSPIQ/FSPIIO7/SUBSPIQ_17") (pintype "passive"))
    )
    (net (code "37") (name "/GPIO14") (class "Default")
      (node (ref "J1") (pin "17") (pinfunction "17_17") (pintype "passive"))
      (node (ref "U1") (pin "18") (pinfunction "GPIO14/RTC_GPIO14/TOUCH14/ADC2_CH3/FSPIWP/FSPIDQS/SUBSPIWP_18") (pintype "passive"))
    )
    (net (code "38") (name "/GPIO15") (class "Default")
      (node (ref "J1") (pin "18") (pinfunction "18_18") (pintype "passive"))
      (node (ref "U1") (pin "19") (pinfunction "GPIO15/RTC_GPIO15/U0RTS/ADC2_CH4/XTAL_32K_P_19") (pintype "passive"))
    )
    (net (code "39") (name "/GPIO16") (class "Default")
      (node (ref "J1") (pin "19") (pinfunction "19_19") (pintype "passive"))
      (node (ref "U1") (pin "20") (pinfunction "GPIO16/RTC_GPIO16/U0CTS/ADC2_CH5/XTAL_32K_N_20") (pintype "passive"))
    )
    (net (code "40") (name "/GPIO17") (class "Default")
      (node (ref "J1") (pin "20") (pinfunction "20_20") (pintype "passive"))
      (node (ref "U1") (pin "21") (pinfunction "GPIO17/RTC_GPIO17/U1TXD/ADC2_CH6_21") (pintype "passive"))
    )
    (net (code "41") (name "/GPIO18") (class "Default")
      (node (ref "J1") (pin "21") (pinfunction "21_21") (pintype "passive"))
      (node (ref "U1") (pin "22") (pinfunction "GPIO18/RTC_GPIO18/U1RXD/ADC2_CH7/CLK_OUT3_22") (pintype "passive"))
    )
    (net (code "42") (name "/GPIO21") (class "Default")
      (node (ref "J2") (pin "19") (pinfunction "19_19") (pintype "passive"))
      (node (ref "U1") (pin "25") (pinfunction "GPIO21/RTC_GPIO21_25") (pintype "passive"))
    )
    (net (code "43") (name "/GPIO26") (class "Default")
      (node (ref "J2") (pin "18") (pinfunction "18_18") (pintype "passive"))
      (node (ref "U1") (pin "26") (pinfunction "GPIO26/SPICS1_26") (pintype "passive"))
    )
    (net (code "44") (name "/GPIO33") (class "Default")
      (node (ref "J2") (pin "17") (pinfunction "17_17") (pintype "passive"))
      (node (ref "U1") (pin "28") (pinfunction "GPIO33/SPIIO4/FSPIHD/SUBSPIHD_28") (pintype "passive"))
    )
    (net (code "45") (name "/GPIO34") (class "Default")
      (node (ref "J2") (pin "16") (pinfunction "16_16") (pintype "passive"))
      (node (ref "U1") (pin "29") (pinfunction "GPIO34/SPIIO5/FSPICS0/SUBSPICS0_29") (pintype "passive"))
    )
    (net (code "46") (name "/GPIO35") (class "Default")
      (node (ref "J2") (pin "15") (pinfunction "15_15") (pintype "passive"))
      (node (ref "U1") (pin "31") (pinfunction "GPIO35/SPIIO6/FSPID/SUBSPID_31") (pintype "passive"))
    )
    (net (code "47") (name "/GPIO36") (class "Default")
      (node (ref "J2") (pin "14") (pinfunction "14_14") (pintype "passive"))
      (node (ref "U1") (pin "32") (pinfunction "GPIO36/SPIIO7/FSPICLK/SUBSPICLK_32") (pintype "passive"))
    )
    (net (code "48") (name "/GPIO37") (class "Default")
      (node (ref "J2") (pin "13") (pinfunction "13_13") (pintype "passive"))
      (node (ref "U1") (pin "33") (pinfunction "GPIO37/SPIDQS/FSPIQ/SUBSPIQ_33") (pintype "passive"))
    )
    (net (code "49") (name "/GPIO38") (class "Default")
      (node (ref "J2") (pin "12") (pinfunction "12_12") (pintype "passive"))
      (node (ref "U1") (pin "34") (pinfunction "GPIO38/FSPIWP/SUBSPIWP_34") (pintype "passive"))
    )
    (net (code "50") (name "/GPIO39") (class "Default")
      (node (ref "J2") (pin "11") (pinfunction "11_11") (pintype "passive"))
      (node (ref "U1") (pin "35") (pinfunction "MTCK/GPIO39/CLK_OUT3/SUBSPICS1_35") (pintype "passive"))
    )
    (net (code "51") (name "/GPIO40") (class "Default")
      (node (ref "J2") (pin "10") (pinfunction "10_10") (pintype "passive"))
      (node (ref "U1") (pin "36") (pinfunction "MTDO/GPIO40/CLK_OUT2_36") (pintype "passive"))
    )
    (net (code "52") (name "/GPIO41") (class "Default")
      (node (ref "J2") (pin "9") (pinfunction "9_9") (pintype "passive"))
      (node (ref "U1") (pin "37") (pinfunction "MTDI/GPIO41/CLK_OUT1_37") (pintype "passive"))
    )
    (net (code "53") (name "/GPIO42") (class "Default")
      (node (ref "J2") (pin "8") (pinfunction "8_8") (pintype "passive"))
      (node (ref "U1") (pin "38") (pinfunction "MTMS/GPIO42_38") (pintype "passive"))
    )
    (net (code "54") (name "/GPIO45") (class "Default")
      (node (ref "J2") (pin "5") (pinfunction "5_5") (pintype "passive"))
      (node (ref "U1") (pin "41") (pinfunction "GPIO45_41") (pintype "passive"))
    )
    (net (code "55") (name "/GPIO46") (class "Default")
      (node (ref "J2") (pin "4") (pinfunction "4_4") (pintype "passive"))
      (node (ref "U1") (pin "44") (pinfunction "GPIO46_44") (pintype "passive"))
    )
    (net (code "56") (name "/GPIO47") (class "Default")
      (node (ref "J2") (pin "23") (pinfunction "23_23") (pintype "passive"))
      (node (ref "U1") (pin "27") (pinfunction "GPIO47/SPICLK_P_DIFF/SUBSPICLK_P_DIFF_27") (pintype "passive"))
    )
    (net (code "57") (name "/GPIO48") (class "Default")
      (node (ref "J2") (pin "22") (pinfunction "22_22") (pintype "passive"))
      (node (ref "U1") (pin "30") (pinfunction "GPIO48/SPICLK_N_DIFF/SUBSPICLK_N_DIFF_30") (pintype "passive"))
    )
    (net (code "58") (name "/RTS_FTDI") (class "Default")
      (node (ref "Q1") (pin "2") (pinfunction "E_2") (pintype "passive"))
      (node (ref "R18") (pin "1") (pinfunction "1_1") (pintype "passive"))
      (node (ref "U2") (pin "19") (pinfunction "~{RTS}_19") (pintype "passive"))
    )
    (net (code "59") (name "/RXD_FTDI") (class "Default")
      (node (ref "R19") (pin "2") (pinfunction "2_2") (pintype "passive"))
      (node (ref "U2") (pin "1") (pinfunction "RXD_1") (pintype "passive"))
    )
    (net (code "60") (name "/TXD_FTDI") (class "Default")
      (node (ref "R20") (pin "2") (pinfunction "2_2") (pintype "passive"))
      (node (ref "U2") (pin "17") (pinfunction "TXD_17") (pintype "passive"))
    )
    (net (code "61") (name "/U0RXD") (class "Default")
      (node (ref "J2") (pin "6") (pinfunction "6_6") (pintype "passive"))
      (node (ref "R20") (pin "1") (pinfunction "1_1") (pintype "passive"))
      (node (ref "U1") (pin "40") (pinfunction "U0RXD/GPIO44/CLK_OUT2_40") (pintype "passive"))
    )
    (net (code "62") (name "/U0TXD") (class "Default")
      (node (ref "J2") (pin "7") (pinfunction "7_7") (pintype "passive"))
      (node (ref "R19") (pin "1") (pinfunction "1_1") (pintype "passive"))
      (node (ref "U1") (pin "39") (pinfunction "U0TXD/GPIO43/CLK_OUT1_39") (pintype "passive"))
    )
    (net (code "63") (name "/VBUS_SENSE") (class "Default")
      (node (ref "R10") (pin "1") (pinfunction "1_1") (pintype "passive"))
      (node (ref "R13") (pin "1") (pinfunction "1_1") (pintype "passive"))
      (node (ref "U2") (pin "16") (pinfunction "CBUS3_16") (pintype "passive"))
    )
    (net (code "64") (name "GND") (class "Default")
      (node (ref "C1") (pin "1") (pinfunction "1_1") (pintype "passive"))
      (node (ref "C10") (pin "1") (pinfunction "1_1") (pintype "passive"))
      (node (ref "C11") (pin "1") (pinfunction "1_1") (pintype "passive"))
      (node (ref "C12") (pin "1") (pinfunction "1_1") (pintype "passive"))
      (node (ref "C13") (pin "1") (pinfunction "1_1") (pintype "passive"))
      (node (ref "C14") (pin "1") (pinfunction "1_1") (pintype "passive"))
      (node (ref "C15") (pin "1") (pinfunction "1_1") (pintype "passive"))
      (node (ref "C16") (pin "1") (pinfunction "1_1") (pintype "passive"))
      (node (ref "C17") (pin "1") (pinfunction "1_1") (pintype "passive"))
      (node (ref "C2") (pin "1") (pinfunction "1_1") (pintype "passive"))
      (node (ref "C3") (pin "1") (pinfunction "1_1") (pintype "passive"))
      (node (ref "C4") (pin "1") (pinfunction "1_1") (pintype "passive"))
      (node (ref "C5") (pin "1") (pinfunction "1_1") (pintype "passive"))
      (node (ref "C6") (pin "1") (pinfunction "1_1") (pintype "passive"))
      (node (ref "C7") (pin "1") (pinfunction "1_1") (pintype "passive"))
      (node (ref "C8") (pin "1") (pinfunction "1_1") (pintype "passive"))
      (node (ref "C9") (pin "1") (pinfunction "1_1") (pintype "passive"))
      (node (ref "D1") (pin "1") (pinfunction "1_1") (pintype "passive"))
      (node (ref "D3") (pin "1") (pinfunction "1_1") (pintype "passive"))
      (node (ref "D4") (pin "1") (pinfunction "1_1") (pintype "passive"))
      (node (ref "D5") (pin "1") (pinfunction "1_1") (pintype "passive"))
      (node (ref "D6") (pin "1") (pinfunction "1_1") (pintype "passive"))
      (node (ref "D7") (pin "1") (pinfunction "1_1") (pintype "passive"))
      (node (ref "D8") (pin "1") (pinfunction "1_1") (pintype "passive"))
      (node (ref "J1") (pin "1") (pinfunction "1_1") (pintype "passive"))
      (node (ref "J1") (pin "23") (pinfunction "23_23") (pintype "passive"))
      (node (ref "J2") (pin "2") (pinfunction "2_2") (pintype "passive"))
      (node (ref "J2") (pin "24") (pinfunction "24_24") (pintype "passive"))
      (node (ref "J3") (pin "A1B12") (pinfunction "GND_A1B12_A1B12") (pintype "passive"))
      (node (ref "J3") (pin "B1A12") (pinfunction "GND_B1A12_B1A12") (pintype "passive"))
      (node (ref "J3") (pin "S1") (pinfunction "SHIELD_1_S1") (pintype "passive"))
      (node (ref "J3") (pin "S2") (pinfunction "SHIELD_2_S2") (pintype "passive"))
      (node (ref "J3") (pin "S3") (pinfunction "SHIELD_3_S3") (pintype "passive"))
      (node (ref "J3") (pin "S4") (pinfunction "SHIELD_4_S4") (pintype "passive"))
      (node (ref "J4") (pin "A1B12") (pinfunction "GND_A1B12_A1B12") (pintype "passive"))
      (node (ref "J4") (pin "B1A12") (pinfunction "GND_B1A12_B1A12") (pintype "passive"))
      (node (ref "J4") (pin "S1") (pinfunction "SHIELD_1_S1") (pintype "passive"))
      (node (ref "J4") (pin "S2") (pinfunction "SHIELD_2_S2") (pintype "passive"))
      (node (ref "J4") (pin "S3") (pinfunction "SHIELD_3_S3") (pintype "passive"))
      (node (ref "J4") (pin "S4") (pinfunction "SHIELD_4_S4") (pintype "passive"))
      (node (ref "R11") (pin "1") (pinfunction "1_1") (pintype "passive"))
      (node (ref "R12") (pin "1") (pinfunction "1_1") (pintype "passive"))
      (node (ref "R13") (pin "2") (pinfunction "2_2") (pintype "passive"))
      (node (ref "R14") (pin "1") (pinfunction "1_1") (pintype "passive"))
      (node (ref "R15") (pin "1") (pinfunction "1_1") (pintype "passive"))
      (node (ref "R9") (pin "2") (pinfunction "2_2") (pintype "passive"))
      (node (ref "SW1") (pin "3") (pinfunction "3_3") (pintype "passive"))
      (node (ref "SW1") (pin "4") (pinfunction "4_4") (pintype "passive"))
      (node (ref "SW2") (pin "3") (pinfunction "3_3") (pintype "passive"))
      (node (ref "SW2") (pin "4") (pinfunction "4_4") (pintype "passive"))
      (node (ref "U1") (pin "1") (pinfunction "GND_01_1") (pintype "passive"))
      (node (ref "U1") (pin "2") (pinfunction "GND_02_2") (pintype "passive"))
      (node (ref "U1") (pin "42") (pinfunction "GND_42") (pintype "passive"))
      (node (ref "U1") (pin "43") (pinfunction "GND_43") (pintype "passive"))
      (node (ref "U1") (pin "46") (pinfunction "GND_46_46") (pintype "passive"))
      (node (ref "U1") (pin "47") (pinfunction "GND_47_47") (pintype "passive"))
      (node (ref "U1") (pin "48") (pinfunction "GND_48_48") (pintype "passive"))
      (node (ref "U1") (pin "49") (pinfunction "GND_49_49") (pintype "passive"))
      (node (ref "U1") (pin "50") (pinfunction "GND_50_50") (pintype "passive"))
      (node (ref "U1") (pin "51") (pinfunction "GND_51_51") (pintype "passive"))
      (node (ref "U1") (pin "52") (pinfunction "GND_52_52") (pintype "passive"))
      (node (ref "U1") (pin "53") (pinfunction "GND_53_53") (pintype "passive"))
      (node (ref "U1") (pin "54") (pinfunction "GND_54_54") (pintype "passive"))
      (node (ref "U1") (pin "55") (pinfunction "GND_55_55") (pintype "passive"))
      (node (ref "U1") (pin "56") (pinfunction "GND_56_56") (pintype "passive"))
      (node (ref "U1") (pin "57") (pinfunction "GND_57_57") (pintype "passive"))
      (node (ref "U1") (pin "58") (pinfunction "GND_58_58") (pintype "passive"))
      (node (ref "U1") (pin "59") (pinfunction "GND_59_59") (pintype "passive"))
      (node (ref "U1") (pin "60") (pinfunction "GND_60_60") (pintype "passive"))
      (node (ref "U1") (pin "61") (pinfunction "GND_61_61") (pintype "passive"))
      (node (ref "U1") (pin "62") (pinfunction "GND_62_62") (pintype "passive"))
      (node (ref "U1") (pin "63") (pinfunction "GND_63_63") (pintype "passive"))
      (node (ref "U1") (pin "64") (pinfunction "GND_64_64") (pintype "passive"))
      (node (ref "U1") (pin "65") (pinfunction "GND_65_65") (pintype "passive"))
      (node (ref "U1") (pin "66") (pinfunction "GND_66_66") (pintype "passive"))
      (node (ref "U1") (pin "67") (pinfunction "GND_67_67") (pintype "passive"))
      (node (ref "U1") (pin "68") (pinfunction "GND_68_68") (pintype "passive"))
      (node (ref "U1") (pin "69") (pinfunction "GND_69_69") (pintype "passive"))
      (node (ref "U1") (pin "70") (pinfunction "GND_70_70") (pintype "passive"))
      (node (ref "U1") (pin "71") (pinfunction "GND_71_71") (pintype "passive"))
      (node (ref "U1") (pin "72") (pinfunction "GND_72_72") (pintype "passive"))
      (node (ref "U1") (pin "73") (pinfunction "GND_73_73") (pintype "passive"))
      (node (ref "U2") (pin "13") (pinfunction "GND_13") (pintype "passive"))
      (node (ref "U2") (pin "21") (pinfunction "GND_21") (pintype "passive"))
      (node (ref "U2") (pin "3") (pinfunction "GND_3") (pintype "passive"))
      (node (ref "U3") (pin "2") (pinfunction "GND_2") (pintype "power_in"))
      (node (ref "U3") (pin "4") (pinfunction "GND_4") (pintype "power_in"))
    )
    (net (code "65") (name "Net-(D1-Pad2)") (class "Default")
      (node (ref "D1") (pin "2") (pinfunction "2_2") (pintype "passive"))
      (node (ref "R3") (pin "1") (pinfunction "1_1") (pintype "passive"))
    )
    (net (code "66") (name "Net-(D2-Pad2)") (class "Default")
      (node (ref "D2") (pin "2") (pinfunction "2_2") (pintype "passive"))
      (node (ref "R4") (pin "1") (pinfunction "1_1") (pintype "passive"))
    )
    (net (code "67") (name "Net-(J3-CC1)") (class "Default")
      (node (ref "J3") (pin "A5") (pinfunction "CC1_A5") (pintype "passive"))
      (node (ref "R12") (pin "2") (pinfunction "2_2") (pintype "passive"))
    )
    (net (code "68") (name "Net-(J3-CC2)") (class "Default")
      (node (ref "J3") (pin "B5") (pinfunction "CC2_B5") (pintype "passive"))
      (node (ref "R11") (pin "2") (pinfunction "2_2") (pintype "passive"))
    )
    (net (code "69") (name "Net-(J4-CC1)") (class "Default")
      (node (ref "J4") (pin "A5") (pinfunction "CC1_A5") (pintype "passive"))
      (node (ref "R15") (pin "2") (pinfunction "2_2") (pintype "passive"))
    )
    (net (code "70") (name "Net-(J4-CC2)") (class "Default")
      (node (ref "J4") (pin "B5") (pinfunction "CC2_B5") (pintype "passive"))
      (node (ref "R14") (pin "2") (pinfunction "2_2") (pintype "passive"))
    )
    (net (code "71") (name "Net-(Q1-B)") (class "Default")
      (node (ref "Q1") (pin "1") (pinfunction "B_1") (pintype "passive"))
      (node (ref "R16") (pin "2") (pinfunction "2_2") (pintype "passive"))
    )
    (net (code "72") (name "Net-(Q2-B)") (class "Default")
      (node (ref "Q2") (pin "1") (pinfunction "B_1") (pintype "passive"))
      (node (ref "R18") (pin "2") (pinfunction "2_2") (pintype "passive"))
    )
    (net (code "73") (name "Net-(U2-CBUS0)") (class "Default")
      (node (ref "R9") (pin "1") (pinfunction "1_1") (pintype "passive"))
      (node (ref "U2") (pin "15") (pinfunction "CBUS0_15") (pintype "passive"))
    )
    (net (code "74") (name "unconnected-(J1-Pad24)") (class "Default")
      (node (ref "J1") (pin "24") (pinfunction "24_24") (pintype "passive+no_connect"))
    )
    (net (code "75") (name "unconnected-(J3-SBU1-PadA8)") (class "Default")
      (node (ref "J3") (pin "A8") (pinfunction "SBU1_A8") (pintype "passive+no_connect"))
    )
    (net (code "76") (name "unconnected-(J3-SBU2-PadB8)") (class "Default")
      (node (ref "J3") (pin "B8") (pinfunction "SBU2_B8") (pintype "passive+no_connect"))
    )
    (net (code "77") (name "unconnected-(J4-SBU1-PadA8)") (class "Default")
      (node (ref "J4") (pin "A8") (pinfunction "SBU1_A8") (pintype "passive+no_connect"))
    )
    (net (code "78") (name "unconnected-(J4-SBU2-PadB8)") (class "Default")
      (node (ref "J4") (pin "B8") (pinfunction "SBU2_B8") (pintype "passive+no_connect"))
    )
    (net (code "79") (name "unconnected-(U2-CBUS1-Pad14)") (class "Default")
      (node (ref "U2") (pin "14") (pinfunction "CBUS1_14") (pintype "passive+no_connect"))
    )
    (net (code "80") (name "unconnected-(U2-CBUS2-Pad7)") (class "Default")
      (node (ref "U2") (pin "7") (pinfunction "CBUS2_7") (pintype "passive+no_connect"))
    )
    (net (code "81") (name "unconnected-(U2-~{CTS}-Pad6)") (class "Default")
      (node (ref "U2") (pin "6") (pinfunction "~{CTS}_6") (pintype "passive+no_connect"))
    )
    (net (code "82") (name "unconnected-(U2-~{DCD}-Pad5)") (class "Default")
      (node (ref "U2") (pin "5") (pinfunction "~{DCD}_5") (pintype "passive+no_connect"))
    )
    (net (code "83") (name "unconnected-(U2-~{DSR}-Pad4)") (class "Default")
      (node (ref "U2") (pin "4") (pinfunction "~{DSR}_4") (pintype "passive+no_connect"))
    )
    (net (code "84") (name "unconnected-(U2-~{RI}-Pad2)") (class "Default")
      (node (ref "U2") (pin "2") (pinfunction "~{RI}_2") (pintype "passive+no_connect"))
    )
  )
)
